# ESP32BMS_Manual.net
KiCad netlist of a schematic drawn in EAGLE
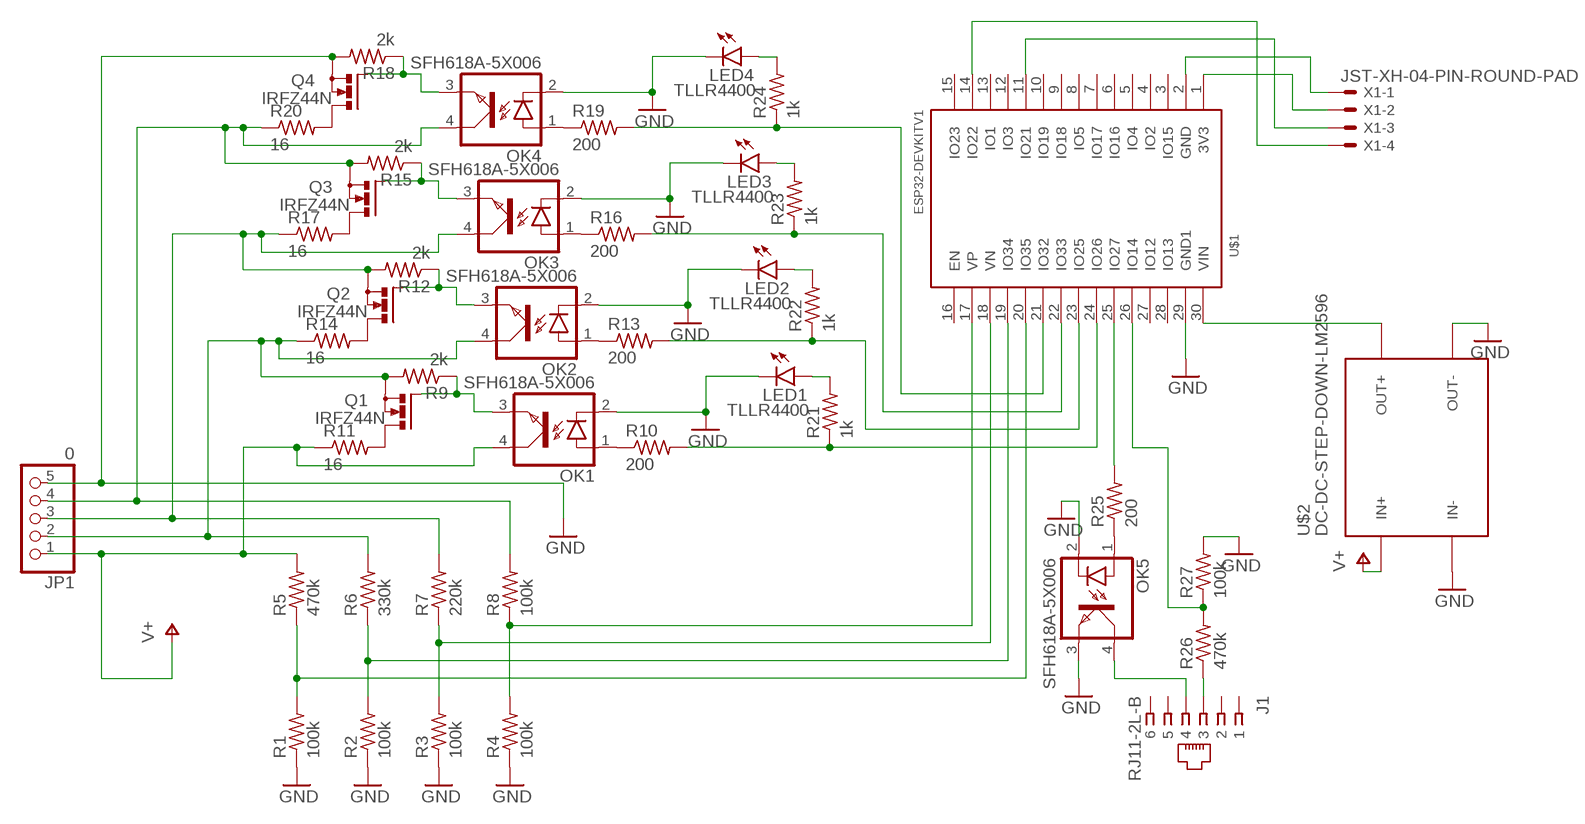
[diagram p0: schematic, sheet 1]

(export (version "E")
  (design (tool "Eeschema 10.0.6"))
  (components
    (comp (ref "J1")
      (value "RJ11-2L-B")
      (footprint "eagle-import:RJ11-NO_SHIELD")
      (fields (field (name "MF") "TYCO ELECTRONICS"))
      (libsource (lib "eagle-import") (part "RJ11-2L-B"))
    )
    (comp (ref "JP1")
      (value "0")
      (footprint "eagle-import:1X05")
      (libsource (lib "eagle-import") (part "PINHD-1X5"))
    )
    (comp (ref "LED1")
      (value "TLLR4400")
      (footprint "eagle-import:LED3MM")
      (fields (field (name "MF") "VISHAY SEMICONDUCTOR"))
      (libsource (lib "eagle-import") (part "TLLR4400"))
    )
    (comp (ref "LED2")
      (value "TLLR4400")
      (footprint "eagle-import:LED3MM")
      (fields (field (name "MF") "VISHAY SEMICONDUCTOR"))
      (libsource (lib "eagle-import") (part "TLLR4400"))
    )
    (comp (ref "LED3")
      (value "TLLR4400")
      (footprint "eagle-import:LED3MM")
      (fields (field (name "MF") "VISHAY SEMICONDUCTOR"))
      (libsource (lib "eagle-import") (part "TLLR4400"))
    )
    (comp (ref "LED4")
      (value "TLLR4400")
      (footprint "eagle-import:LED3MM")
      (fields (field (name "MF") "VISHAY SEMICONDUCTOR"))
      (libsource (lib "eagle-import") (part "TLLR4400"))
    )
    (comp (ref "OK1")
      (value "SFH618A-5X006")
      (footprint "eagle-import:DIP4-400")
      (libsource (lib "eagle-import") (part "SFH618?A-5X006"))
    )
    (comp (ref "OK2")
      (value "SFH618A-5X006")
      (footprint "eagle-import:DIP4-400")
      (libsource (lib "eagle-import") (part "SFH618?A-5X006"))
    )
    (comp (ref "OK3")
      (value "SFH618A-5X006")
      (footprint "eagle-import:DIP4-400")
      (libsource (lib "eagle-import") (part "SFH618?A-5X006"))
    )
    (comp (ref "OK4")
      (value "SFH618A-5X006")
      (footprint "eagle-import:DIP4-400")
      (libsource (lib "eagle-import") (part "SFH618?A-5X006"))
    )
    (comp (ref "OK5")
      (value "SFH618A-5X006")
      (footprint "eagle-import:DIP4-400")
      (libsource (lib "eagle-import") (part "SFH618?A-5X006"))
    )
    (comp (ref "Q1")
      (value "IRFZ44N")
      (footprint "eagle-import:TO220BV")
      (libsource (lib "eagle-import") (part "PMOSFET_NTO220BV"))
    )
    (comp (ref "Q2")
      (value "IRFZ44N")
      (footprint "eagle-import:TO220BV")
      (libsource (lib "eagle-import") (part "PMOSFET_NTO220BV"))
    )
    (comp (ref "Q3")
      (value "IRFZ44N")
      (footprint "eagle-import:TO220BV")
      (libsource (lib "eagle-import") (part "PMOSFET_NTO220BV"))
    )
    (comp (ref "Q4")
      (value "IRFZ44N")
      (footprint "eagle-import:TO220BV")
      (libsource (lib "eagle-import") (part "PMOSFET_NTO220BV"))
    )
    (comp (ref "R1")
      (value "100k")
      (footprint "eagle-import:0204_7")
      (libsource (lib "eagle-import") (part "R-US_0204/7"))
    )
    (comp (ref "R2")
      (value "100k")
      (footprint "eagle-import:0204_7")
      (libsource (lib "eagle-import") (part "R-US_0204/7"))
    )
    (comp (ref "R3")
      (value "100k")
      (footprint "eagle-import:0204_7")
      (libsource (lib "eagle-import") (part "R-US_0204/7"))
    )
    (comp (ref "R4")
      (value "100k")
      (footprint "eagle-import:0204_7")
      (libsource (lib "eagle-import") (part "R-US_0204/7"))
    )
    (comp (ref "R5")
      (value "470k")
      (footprint "eagle-import:0204_7")
      (libsource (lib "eagle-import") (part "R-US_0204/7"))
    )
    (comp (ref "R6")
      (value "330k")
      (footprint "eagle-import:0204_7")
      (libsource (lib "eagle-import") (part "R-US_0204/7"))
    )
    (comp (ref "R7")
      (value "220k")
      (footprint "eagle-import:0204_7")
      (libsource (lib "eagle-import") (part "R-US_0204/7"))
    )
    (comp (ref "R8")
      (value "100k")
      (footprint "eagle-import:0204_7")
      (libsource (lib "eagle-import") (part "R-US_0204/7"))
    )
    (comp (ref "R9")
      (value "2k")
      (footprint "eagle-import:0204_7")
      (libsource (lib "eagle-import") (part "R-US_0204/7"))
    )
    (comp (ref "R10")
      (value "200")
      (footprint "eagle-import:0204_7")
      (libsource (lib "eagle-import") (part "R-US_0204/7"))
    )
    (comp (ref "R11")
      (value "16")
      (footprint "eagle-import:0414V")
      (libsource (lib "eagle-import") (part "R-US_0414/5V"))
    )
    (comp (ref "R12")
      (value "2k")
      (footprint "eagle-import:0204_7")
      (libsource (lib "eagle-import") (part "R-US_0204/7"))
    )
    (comp (ref "R13")
      (value "200")
      (footprint "eagle-import:0204_7")
      (libsource (lib "eagle-import") (part "R-US_0204/7"))
    )
    (comp (ref "R14")
      (value "16")
      (footprint "eagle-import:0414V")
      (libsource (lib "eagle-import") (part "R-US_0414/5V"))
    )
    (comp (ref "R15")
      (value "2k")
      (footprint "eagle-import:0204_7")
      (libsource (lib "eagle-import") (part "R-US_0204/7"))
    )
    (comp (ref "R16")
      (value "200")
      (footprint "eagle-import:0204_7")
      (libsource (lib "eagle-import") (part "R-US_0204/7"))
    )
    (comp (ref "R17")
      (value "16")
      (footprint "eagle-import:0414V")
      (libsource (lib "eagle-import") (part "R-US_0414/5V"))
    )
    (comp (ref "R18")
      (value "2k")
      (footprint "eagle-import:0204_7")
      (libsource (lib "eagle-import") (part "R-US_0204/7"))
    )
    (comp (ref "R19")
      (value "200")
      (footprint "eagle-import:0204_7")
      (libsource (lib "eagle-import") (part "R-US_0204/7"))
    )
    (comp (ref "R20")
      (value "16")
      (footprint "eagle-import:0414V")
      (libsource (lib "eagle-import") (part "R-US_0414/5V"))
    )
    (comp (ref "R21")
      (value "1k")
      (footprint "eagle-import:0204_7")
      (libsource (lib "eagle-import") (part "R-US_0204/7"))
    )
    (comp (ref "R22")
      (value "1k")
      (footprint "eagle-import:0204_7")
      (libsource (lib "eagle-import") (part "R-US_0204/7"))
    )
    (comp (ref "R23")
      (value "1k")
      (footprint "eagle-import:0204_7")
      (libsource (lib "eagle-import") (part "R-US_0204/7"))
    )
    (comp (ref "R24")
      (value "1k")
      (footprint "eagle-import:0204_7")
      (libsource (lib "eagle-import") (part "R-US_0204/7"))
    )
    (comp (ref "R25")
      (value "200")
      (footprint "eagle-import:0204_7")
      (libsource (lib "eagle-import") (part "R-US_0204/7"))
    )
    (comp (ref "R26")
      (value "470k")
      (footprint "eagle-import:0204_7")
      (libsource (lib "eagle-import") (part "R-US_0204/7"))
    )
    (comp (ref "R27")
      (value "100k")
      (footprint "eagle-import:0204_7")
      (libsource (lib "eagle-import") (part "R-US_0204/7"))
    )
    (comp (ref "U$1")
      (value "ESP32DEVKITV1")
      (footprint "eagle-import:ESP32-DEVKITV1")
      (libsource (lib "eagle-import") (part "ESP32DEVKITV1"))
    )
    (comp (ref "U$2")
      (value "DC-DC-STEP-DOWN-LM2596")
      (footprint "eagle-import:DC-DC-STEP-DOWN-LM2596")
      (libsource (lib "eagle-import") (part "DC-DC-STEP-DOWN-LM2596"))
    )
    (comp (ref "X1")
      (value "JST-XH-04-PIN-ROUND-PAD")
      (footprint "eagle-import:JST-XH-04-PACKAGE-ROUND-PAD")
      (libsource (lib "eagle-import") (part "JST-XH-04-PIN-ROUND-PAD"))
    )
  )
  (nets
    (net (code "1") (name "GND") (class "Default")
      (node (ref "JP1") (pin "5") (pinfunction "5_5") (pintype "passive"))
      (node (ref "LED1") (pin "K") (pinfunction "C_K") (pintype "passive"))
      (node (ref "LED2") (pin "K") (pinfunction "C_K") (pintype "passive"))
      (node (ref "LED3") (pin "K") (pinfunction "C_K") (pintype "passive"))
      (node (ref "LED4") (pin "K") (pinfunction "C_K") (pintype "passive"))
      (node (ref "OK1") (pin "2") (pinfunction "C_2") (pintype "passive"))
      (node (ref "OK2") (pin "2") (pinfunction "C_2") (pintype "passive"))
      (node (ref "OK3") (pin "2") (pinfunction "C_2") (pintype "passive"))
      (node (ref "OK4") (pin "2") (pinfunction "C_2") (pintype "passive"))
      (node (ref "OK5") (pin "2") (pinfunction "C_2") (pintype "passive"))
      (node (ref "OK5") (pin "3") (pinfunction "EMIT_3") (pintype "passive"))
      (node (ref "Q4") (pin "S") (pinfunction "S_S") (pintype "passive"))
      (node (ref "R1") (pin "1") (pinfunction "1_1") (pintype "passive"))
      (node (ref "R18") (pin "2") (pinfunction "2_2") (pintype "passive"))
      (node (ref "R2") (pin "1") (pinfunction "1_1") (pintype "passive"))
      (node (ref "R27") (pin "2") (pinfunction "2_2") (pintype "passive"))
      (node (ref "R3") (pin "1") (pinfunction "1_1") (pintype "passive"))
      (node (ref "R4") (pin "1") (pinfunction "1_1") (pintype "passive"))
      (node (ref "U$1") (pin "29") (pinfunction "GND1_29") (pintype "bidirectional"))
      (node (ref "U$2") (pin "IN-") (pinfunction "IN-_IN-") (pintype "bidirectional"))
      (node (ref "U$2") (pin "OUT-") (pinfunction "OUT-_OUT-") (pintype "bidirectional"))
    )
    (net (code "2") (name "Net-(J1-Pad3)") (class "Default")
      (node (ref "J1") (pin "3") (pinfunction "3_3") (pintype "passive"))
      (node (ref "R26") (pin "1") (pinfunction "1_1") (pintype "passive"))
    )
    (net (code "3") (name "Net-(LED1-PadA)") (class "Default")
      (node (ref "LED1") (pin "A") (pinfunction "A_A") (pintype "passive"))
      (node (ref "R21") (pin "2") (pinfunction "2_2") (pintype "passive"))
    )
    (net (code "4") (name "Net-(LED2-PadA)") (class "Default")
      (node (ref "LED2") (pin "A") (pinfunction "A_A") (pintype "passive"))
      (node (ref "R22") (pin "2") (pinfunction "2_2") (pintype "passive"))
    )
    (net (code "5") (name "Net-(LED3-PadA)") (class "Default")
      (node (ref "LED3") (pin "A") (pinfunction "A_A") (pintype "passive"))
      (node (ref "R23") (pin "2") (pinfunction "2_2") (pintype "passive"))
    )
    (net (code "6") (name "Net-(LED4-PadA)") (class "Default")
      (node (ref "LED4") (pin "A") (pinfunction "A_A") (pintype "passive"))
      (node (ref "R24") (pin "2") (pinfunction "2_2") (pintype "passive"))
    )
    (net (code "7") (name "Net-(OK1-A)") (class "Default")
      (node (ref "OK1") (pin "1") (pinfunction "A_1") (pintype "passive"))
      (node (ref "R10") (pin "1") (pinfunction "1_1") (pintype "passive"))
    )
    (net (code "8") (name "Net-(OK1-EMIT)") (class "Default")
      (node (ref "OK1") (pin "3") (pinfunction "EMIT_3") (pintype "passive"))
      (node (ref "Q1") (pin "G") (pinfunction "G_G") (pintype "passive"))
      (node (ref "R9") (pin "1") (pinfunction "1_1") (pintype "passive"))
    )
    (net (code "9") (name "Net-(OK2-A)") (class "Default")
      (node (ref "OK2") (pin "1") (pinfunction "A_1") (pintype "passive"))
      (node (ref "R13") (pin "1") (pinfunction "1_1") (pintype "passive"))
    )
    (net (code "10") (name "Net-(OK2-COL)") (class "Default")
      (node (ref "JP1") (pin "2") (pinfunction "2_2") (pintype "passive"))
      (node (ref "OK2") (pin "4") (pinfunction "COL_4") (pintype "passive"))
      (node (ref "Q1") (pin "S") (pinfunction "S_S") (pintype "passive"))
      (node (ref "R14") (pin "1") (pinfunction "1_1") (pintype "passive"))
      (node (ref "R6") (pin "2") (pinfunction "2_2") (pintype "passive"))
      (node (ref "R9") (pin "2") (pinfunction "2_2") (pintype "passive"))
    )
    (net (code "11") (name "Net-(OK2-EMIT)") (class "Default")
      (node (ref "OK2") (pin "3") (pinfunction "EMIT_3") (pintype "passive"))
      (node (ref "Q2") (pin "G") (pinfunction "G_G") (pintype "passive"))
      (node (ref "R12") (pin "1") (pinfunction "1_1") (pintype "passive"))
    )
    (net (code "12") (name "Net-(OK3-A)") (class "Default")
      (node (ref "OK3") (pin "1") (pinfunction "A_1") (pintype "passive"))
      (node (ref "R16") (pin "1") (pinfunction "1_1") (pintype "passive"))
    )
    (net (code "13") (name "Net-(OK3-COL)") (class "Default")
      (node (ref "JP1") (pin "3") (pinfunction "3_3") (pintype "passive"))
      (node (ref "OK3") (pin "4") (pinfunction "COL_4") (pintype "passive"))
      (node (ref "Q2") (pin "S") (pinfunction "S_S") (pintype "passive"))
      (node (ref "R12") (pin "2") (pinfunction "2_2") (pintype "passive"))
      (node (ref "R17") (pin "1") (pinfunction "1_1") (pintype "passive"))
      (node (ref "R7") (pin "2") (pinfunction "2_2") (pintype "passive"))
    )
    (net (code "14") (name "Net-(OK3-EMIT)") (class "Default")
      (node (ref "OK3") (pin "3") (pinfunction "EMIT_3") (pintype "passive"))
      (node (ref "Q3") (pin "G") (pinfunction "G_G") (pintype "passive"))
      (node (ref "R15") (pin "1") (pinfunction "1_1") (pintype "passive"))
    )
    (net (code "15") (name "Net-(OK4-A)") (class "Default")
      (node (ref "OK4") (pin "1") (pinfunction "A_1") (pintype "passive"))
      (node (ref "R19") (pin "1") (pinfunction "1_1") (pintype "passive"))
    )
    (net (code "16") (name "Net-(OK4-COL)") (class "Default")
      (node (ref "JP1") (pin "4") (pinfunction "4_4") (pintype "passive"))
      (node (ref "OK4") (pin "4") (pinfunction "COL_4") (pintype "passive"))
      (node (ref "Q3") (pin "S") (pinfunction "S_S") (pintype "passive"))
      (node (ref "R15") (pin "2") (pinfunction "2_2") (pintype "passive"))
      (node (ref "R20") (pin "1") (pinfunction "1_1") (pintype "passive"))
      (node (ref "R8") (pin "2") (pinfunction "2_2") (pintype "passive"))
    )
    (net (code "17") (name "Net-(OK4-EMIT)") (class "Default")
      (node (ref "OK4") (pin "3") (pinfunction "EMIT_3") (pintype "passive"))
      (node (ref "Q4") (pin "G") (pinfunction "G_G") (pintype "passive"))
      (node (ref "R18") (pin "1") (pinfunction "1_1") (pintype "passive"))
    )
    (net (code "18") (name "Net-(OK5-A)") (class "Default")
      (node (ref "OK5") (pin "1") (pinfunction "A_1") (pintype "passive"))
      (node (ref "R25") (pin "1") (pinfunction "1_1") (pintype "passive"))
    )
    (net (code "19") (name "Net-(OK5-COL)") (class "Default")
      (node (ref "J1") (pin "4") (pinfunction "4_4") (pintype "passive"))
      (node (ref "OK5") (pin "4") (pinfunction "COL_4") (pintype "passive"))
    )
    (net (code "20") (name "Net-(Q1-PadD)") (class "Default")
      (node (ref "Q1") (pin "D") (pinfunction "D_D") (pintype "passive"))
      (node (ref "R11") (pin "2") (pinfunction "2_2") (pintype "passive"))
    )
    (net (code "21") (name "Net-(Q2-PadD)") (class "Default")
      (node (ref "Q2") (pin "D") (pinfunction "D_D") (pintype "passive"))
      (node (ref "R14") (pin "2") (pinfunction "2_2") (pintype "passive"))
    )
    (net (code "22") (name "Net-(Q3-PadD)") (class "Default")
      (node (ref "Q3") (pin "D") (pinfunction "D_D") (pintype "passive"))
      (node (ref "R17") (pin "2") (pinfunction "2_2") (pintype "passive"))
    )
    (net (code "23") (name "Net-(Q4-PadD)") (class "Default")
      (node (ref "Q4") (pin "D") (pinfunction "D_D") (pintype "passive"))
      (node (ref "R20") (pin "2") (pinfunction "2_2") (pintype "passive"))
    )
    (net (code "24") (name "Net-(U$1-3V3)") (class "Default")
      (node (ref "U$1") (pin "1") (pinfunction "3V3_1") (pintype "bidirectional"))
      (node (ref "X1") (pin "2") (pinfunction "S_2") (pintype "passive"))
    )
    (net (code "25") (name "Net-(U$1-GND)") (class "Default")
      (node (ref "U$1") (pin "2") (pinfunction "GND_2") (pintype "bidirectional"))
      (node (ref "X1") (pin "1") (pinfunction "S_1") (pintype "passive"))
    )
    (net (code "26") (name "Net-(U$1-IO14)") (class "Default")
      (node (ref "R26") (pin "2") (pinfunction "2_2") (pintype "passive"))
      (node (ref "R27") (pin "1") (pinfunction "1_1") (pintype "passive"))
      (node (ref "U$1") (pin "26") (pinfunction "IO14_26") (pintype "bidirectional"))
    )
    (net (code "27") (name "Net-(U$1-IO21)") (class "Default")
      (node (ref "U$1") (pin "11") (pinfunction "IO21_11") (pintype "bidirectional"))
      (node (ref "X1") (pin "3") (pinfunction "S_3") (pintype "passive"))
    )
    (net (code "28") (name "Net-(U$1-IO22)") (class "Default")
      (node (ref "U$1") (pin "14") (pinfunction "IO22_14") (pintype "bidirectional"))
      (node (ref "X1") (pin "4") (pinfunction "S_4") (pintype "passive"))
    )
    (net (code "29") (name "Net-(U$1-IO25)") (class "Default")
      (node (ref "R13") (pin "2") (pinfunction "2_2") (pintype "passive"))
      (node (ref "R22") (pin "1") (pinfunction "1_1") (pintype "passive"))
      (node (ref "U$1") (pin "23") (pinfunction "IO25_23") (pintype "bidirectional"))
    )
    (net (code "30") (name "Net-(U$1-IO26)") (class "Default")
      (node (ref "R10") (pin "2") (pinfunction "2_2") (pintype "passive"))
      (node (ref "R21") (pin "1") (pinfunction "1_1") (pintype "passive"))
      (node (ref "U$1") (pin "24") (pinfunction "IO26_24") (pintype "bidirectional"))
    )
    (net (code "31") (name "Net-(U$1-IO27)") (class "Default")
      (node (ref "R25") (pin "2") (pinfunction "2_2") (pintype "passive"))
      (node (ref "U$1") (pin "25") (pinfunction "IO27_25") (pintype "bidirectional"))
    )
    (net (code "32") (name "Net-(U$1-IO32)") (class "Default")
      (node (ref "R19") (pin "2") (pinfunction "2_2") (pintype "passive"))
      (node (ref "R24") (pin "1") (pinfunction "1_1") (pintype "passive"))
      (node (ref "U$1") (pin "21") (pinfunction "IO32_21") (pintype "bidirectional"))
    )
    (net (code "33") (name "Net-(U$1-IO33)") (class "Default")
      (node (ref "R16") (pin "2") (pinfunction "2_2") (pintype "passive"))
      (node (ref "R23") (pin "1") (pinfunction "1_1") (pintype "passive"))
      (node (ref "U$1") (pin "22") (pinfunction "IO33_22") (pintype "bidirectional"))
    )
    (net (code "34") (name "Net-(U$1-IO34)") (class "Default")
      (node (ref "R2") (pin "2") (pinfunction "2_2") (pintype "passive"))
      (node (ref "R6") (pin "1") (pinfunction "1_1") (pintype "passive"))
      (node (ref "U$1") (pin "19") (pinfunction "IO34_19") (pintype "bidirectional"))
    )
    (net (code "35") (name "Net-(U$1-IO35)") (class "Default")
      (node (ref "R1") (pin "2") (pinfunction "2_2") (pintype "passive"))
      (node (ref "R5") (pin "1") (pinfunction "1_1") (pintype "passive"))
      (node (ref "U$1") (pin "20") (pinfunction "IO35_20") (pintype "bidirectional"))
    )
    (net (code "36") (name "Net-(U$1-VIN)") (class "Default")
      (node (ref "U$1") (pin "30") (pinfunction "VIN_30") (pintype "bidirectional"))
      (node (ref "U$2") (pin "OUT+") (pinfunction "OUT+_OUT+") (pintype "bidirectional"))
    )
    (net (code "37") (name "Net-(U$1-VN)") (class "Default")
      (node (ref "R3") (pin "2") (pinfunction "2_2") (pintype "passive"))
      (node (ref "R7") (pin "1") (pinfunction "1_1") (pintype "passive"))
      (node (ref "U$1") (pin "18") (pinfunction "VN_18") (pintype "bidirectional"))
    )
    (net (code "38") (name "Net-(U$1-VP)") (class "Default")
      (node (ref "R4") (pin "2") (pinfunction "2_2") (pintype "passive"))
      (node (ref "R8") (pin "1") (pinfunction "1_1") (pintype "passive"))
      (node (ref "U$1") (pin "17") (pinfunction "VP_17") (pintype "bidirectional"))
    )
    (net (code "39") (name "V+") (class "Default")
      (node (ref "JP1") (pin "1") (pinfunction "1_1") (pintype "passive"))
      (node (ref "OK1") (pin "4") (pinfunction "COL_4") (pintype "passive"))
      (node (ref "R11") (pin "1") (pinfunction "1_1") (pintype "passive"))
      (node (ref "R5") (pin "2") (pinfunction "2_2") (pintype "passive"))
      (node (ref "U$2") (pin "IN+") (pinfunction "IN+_IN+") (pintype "bidirectional"))
    )
    (net (code "40") (name "unconnected-(J1-Pad1)") (class "Default")
      (node (ref "J1") (pin "1") (pinfunction "1_1") (pintype "passive"))
    )
    (net (code "41") (name "unconnected-(J1-Pad2)") (class "Default")
      (node (ref "J1") (pin "2") (pinfunction "2_2") (pintype "passive"))
    )
    (net (code "42") (name "unconnected-(J1-Pad5)") (class "Default")
      (node (ref "J1") (pin "5") (pinfunction "5_5") (pintype "passive"))
    )
    (net (code "43") (name "unconnected-(J1-Pad6)") (class "Default")
      (node (ref "J1") (pin "6") (pinfunction "6_6") (pintype "passive"))
    )
    (net (code "44") (name "unconnected-(U$1-EN-Pad16)") (class "Default")
      (node (ref "U$1") (pin "16") (pinfunction "EN_16") (pintype "bidirectional"))
    )
    (net (code "45") (name "unconnected-(U$1-IO1-Pad13)") (class "Default")
      (node (ref "U$1") (pin "13") (pinfunction "IO1_13") (pintype "bidirectional"))
    )
    (net (code "46") (name "unconnected-(U$1-IO2-Pad4)") (class "Default")
      (node (ref "U$1") (pin "4") (pinfunction "IO2_4") (pintype "bidirectional"))
    )
    (net (code "47") (name "unconnected-(U$1-IO3-Pad12)") (class "Default")
      (node (ref "U$1") (pin "12") (pinfunction "IO3_12") (pintype "bidirectional"))
    )
    (net (code "48") (name "unconnected-(U$1-IO4-Pad5)") (class "Default")
      (node (ref "U$1") (pin "5") (pinfunction "IO4_5") (pintype "bidirectional"))
    )
    (net (code "49") (name "unconnected-(U$1-IO5-Pad8)") (class "Default")
      (node (ref "U$1") (pin "8") (pinfunction "IO5_8") (pintype "bidirectional"))
    )
    (net (code "50") (name "unconnected-(U$1-IO12-Pad27)") (class "Default")
      (node (ref "U$1") (pin "27") (pinfunction "IO12_27") (pintype "bidirectional"))
    )
    (net (code "51") (name "unconnected-(U$1-IO13-Pad28)") (class "Default")
      (node (ref "U$1") (pin "28") (pinfunction "IO13_28") (pintype "bidirectional"))
    )
    (net (code "52") (name "unconnected-(U$1-IO15-Pad3)") (class "Default")
      (node (ref "U$1") (pin "3") (pinfunction "IO15_3") (pintype "bidirectional"))
    )
    (net (code "53") (name "unconnected-(U$1-IO16-Pad6)") (class "Default")
      (node (ref "U$1") (pin "6") (pinfunction "IO16_6") (pintype "bidirectional"))
    )
    (net (code "54") (name "unconnected-(U$1-IO17-Pad7)") (class "Default")
      (node (ref "U$1") (pin "7") (pinfunction "IO17_7") (pintype "bidirectional"))
    )
    (net (code "55") (name "unconnected-(U$1-IO18-Pad9)") (class "Default")
      (node (ref "U$1") (pin "9") (pinfunction "IO18_9") (pintype "bidirectional"))
    )
    (net (code "56") (name "unconnected-(U$1-IO19-Pad10)") (class "Default")
      (node (ref "U$1") (pin "10") (pinfunction "IO19_10") (pintype "bidirectional"))
    )
    (net (code "57") (name "unconnected-(U$1-IO23-Pad15)") (class "Default")
      (node (ref "U$1") (pin "15") (pinfunction "IO23_15") (pintype "bidirectional"))
    )
  )
)
